# power_test.net
KiCad netlist of a schematic drawn in EAGLE
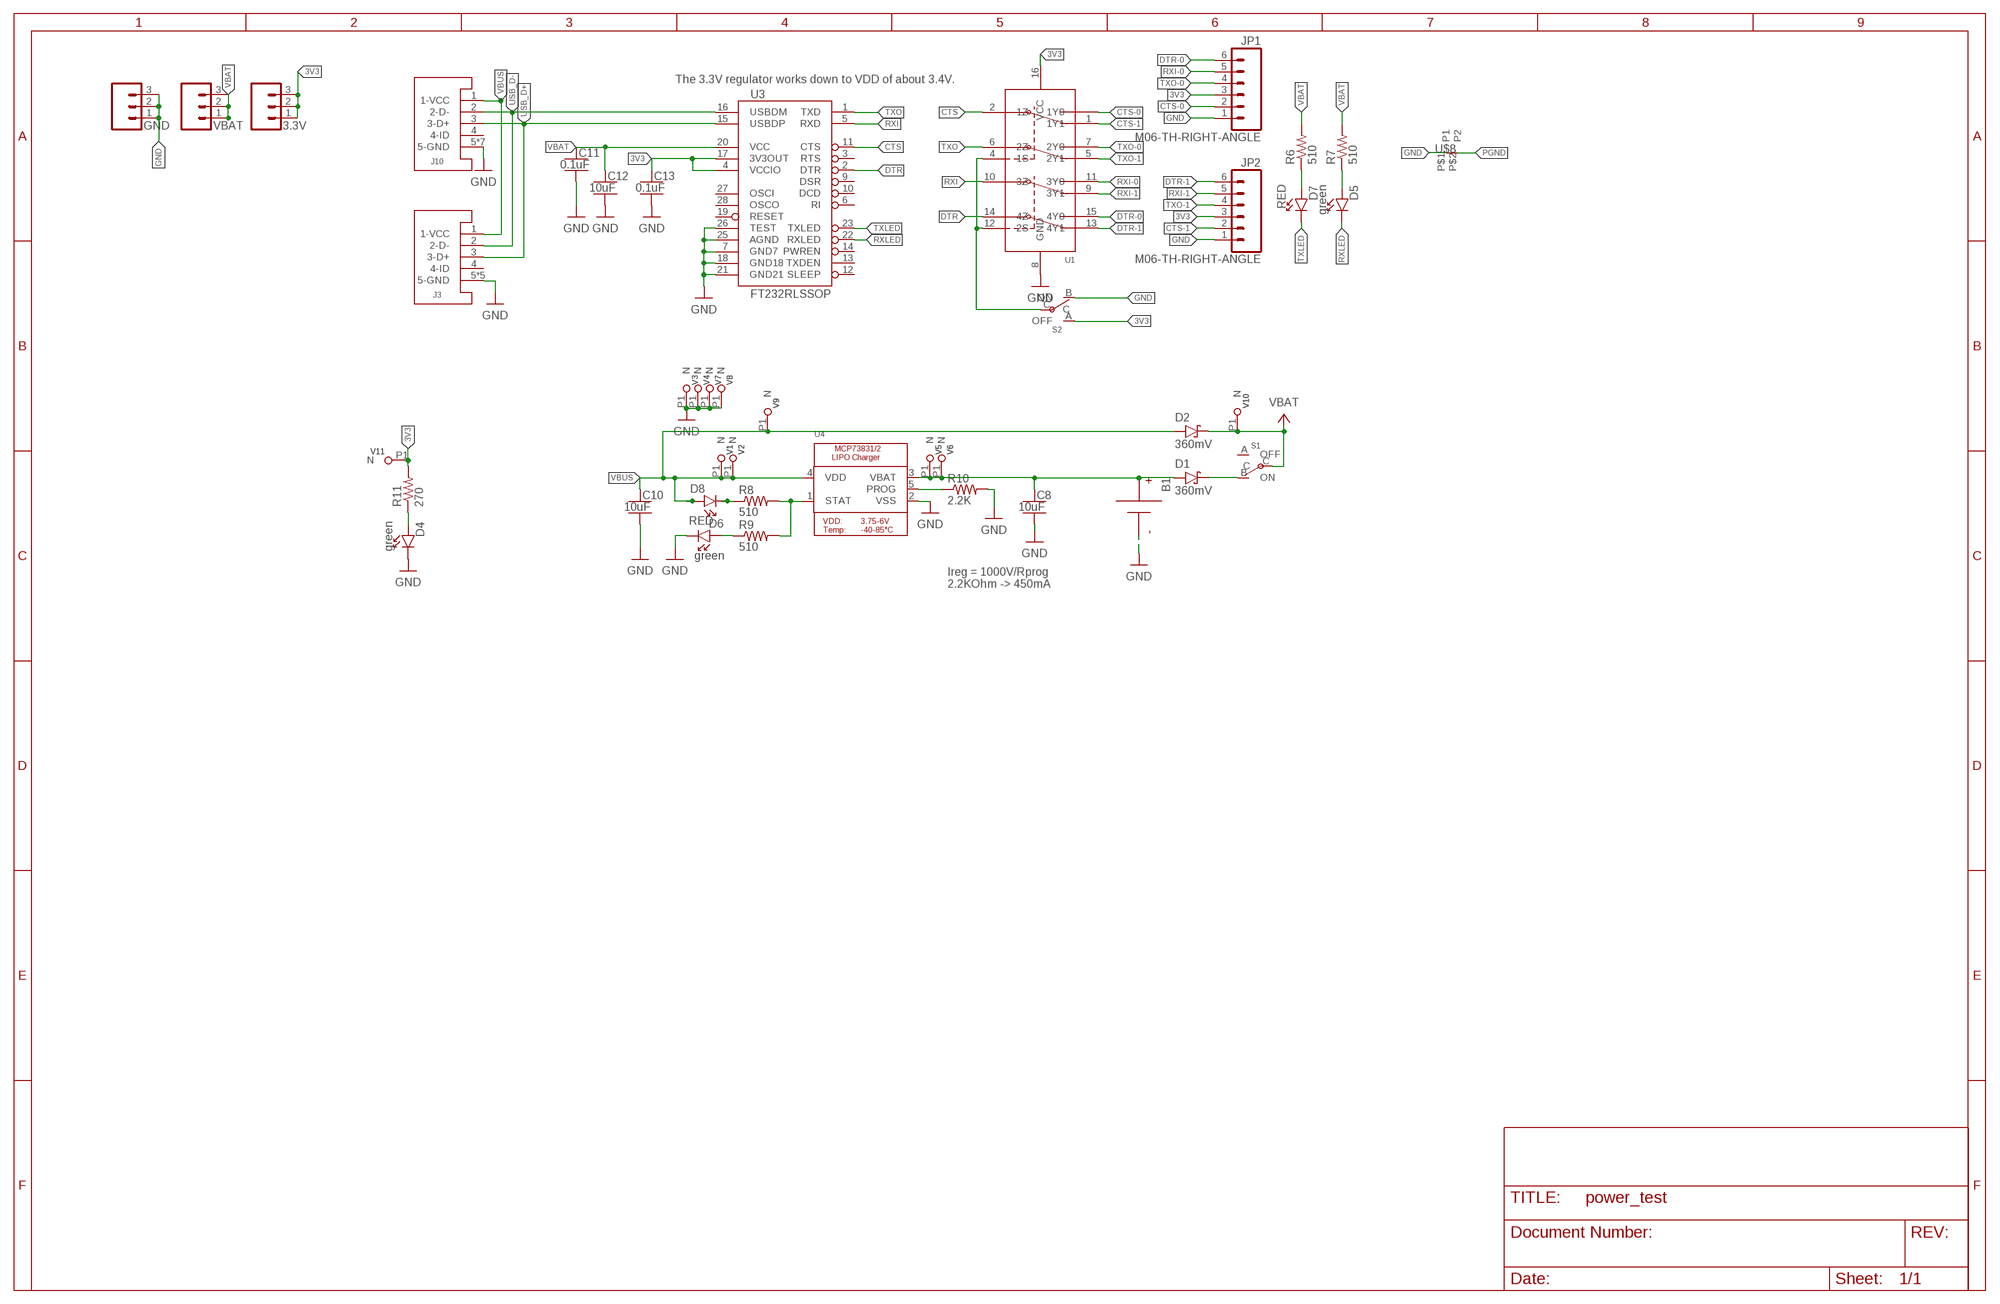
[diagram p0: schematic, sheet 1]

(export (version "E")
  (design (tool "Eeschema 10.0.6"))
  (components
    (comp (ref "3.3V")
      (value "HEADER-0.1IN-3POS-MALE")
      (footprint "eagle-import:HDRV3W63P254_3X1_762X254H838_HS")
      (libsource (lib "eagle-import") (part "HEADER-0.1IN-3POS-MALE"))
    )
    (comp (ref "B1")
      (value "BATTERY")
      (footprint "eagle-import:BATTERY-TERMINALS")
      (fields (field (name "CREATOR") "Swanson"))
      (libsource (lib "eagle-import") (part "BATTERY"))
    )
    (comp (ref "C8")
      (value "10uF")
      (footprint "eagle-import:CAPC2012X140_HS")
      (fields
        (field (name "MFR") "TDK Corporation")
        (field (name "MPN") "C2012X5R1E106K085AC")
        (field (name "CREATOR") "Swanson")
        (field (name "REVIEWER") "Swanson")
      )
      (libsource (lib "eagle-import") (part "CAPACITOR-NP_SMD-2012-0805_CERAMIC-10UF"))
    )
    (comp (ref "C10")
      (value "10uF")
      (footprint "eagle-import:CAPC2012X140_HS")
      (fields
        (field (name "MFR") "TDK Corporation")
        (field (name "MPN") "C2012X5R1E106K085AC")
        (field (name "CREATOR") "Swanson")
        (field (name "REVIEWER") "Swanson")
      )
      (libsource (lib "eagle-import") (part "CAPACITOR-NP_SMD-2012-0805_CERAMIC-10UF"))
    )
    (comp (ref "C11")
      (value "0.1uF")
      (footprint "eagle-import:CAPC2012X140_HS")
      (fields
        (field (name "MFR") "TDK")
        (field (name "MPN") "C2012X7R2A104K125AA")
        (field (name "CREATOR") "Swanson")
        (field (name "REVIEWER") "Swanson")
      )
      (libsource (lib "eagle-import") (part "CAPACITOR-NP_SMD-2012-0805_CERAMIC-0.1UF"))
    )
    (comp (ref "C12")
      (value "10uF")
      (footprint "eagle-import:CAPC2012X140_HS")
      (fields
        (field (name "MFR") "TDK Corporation")
        (field (name "MPN") "C2012X5R1E106K085AC")
        (field (name "CREATOR") "Swanson")
        (field (name "REVIEWER") "Swanson")
      )
      (libsource (lib "eagle-import") (part "CAPACITOR-NP_SMD-2012-0805_CERAMIC-10UF"))
    )
    (comp (ref "C13")
      (value "0.1uF")
      (footprint "eagle-import:CAPC2012X140_HS")
      (fields
        (field (name "MFR") "TDK")
        (field (name "MPN") "C2012X7R2A104K125AA")
        (field (name "CREATOR") "Swanson")
        (field (name "REVIEWER") "Swanson")
      )
      (libsource (lib "eagle-import") (part "CAPACITOR-NP_SMD-2012-0805_CERAMIC-0.1UF"))
    )
    (comp (ref "D1")
      (value "360mV")
      (footprint "eagle-import:SOD3716X135_HS")
      (fields
        (field (name "MFR") "Toshiba Semiconductor and Storage")
        (field (name "MPN") "CRS08(TE85L,Q,M)")
        (field (name "CREATOR") "Swanson")
        (field (name "REVIEWER") "Swanson")
      )
      (libsource (lib "eagle-import") (part "DIODE-SCHOTTKY_SMD-SOD123-360MV"))
    )
    (comp (ref "D2")
      (value "360mV")
      (footprint "eagle-import:SOD3716X135_HS")
      (fields
        (field (name "MFR") "Toshiba Semiconductor and Storage")
        (field (name "MPN") "CRS08(TE85L,Q,M)")
        (field (name "CREATOR") "Swanson")
        (field (name "REVIEWER") "Swanson")
      )
      (libsource (lib "eagle-import") (part "DIODE-SCHOTTKY_SMD-SOD123-360MV"))
    )
    (comp (ref "D4")
      (value "green")
      (footprint "eagle-import:LEDSC125X200X120-2_HS")
      (fields
        (field (name "MFR") "Lite-On Inc")
        (field (name "MPN") "LTST-C170GKT")
        (field (name "CREATOR") "Swanson")
        (field (name "REVIEWER") "Swanson")
      )
      (libsource (lib "eagle-import") (part "DIODE-LED_SMD-2012-0805-GREEN"))
    )
    (comp (ref "D5")
      (value "green")
      (footprint "eagle-import:LEDSC125X200X120-2_HS")
      (fields
        (field (name "MFR") "Lite-On Inc")
        (field (name "MPN") "LTST-C170GKT")
        (field (name "CREATOR") "Swanson")
        (field (name "REVIEWER") "Swanson")
      )
      (libsource (lib "eagle-import") (part "DIODE-LED_SMD-2012-0805-GREEN"))
    )
    (comp (ref "D6")
      (value "green")
      (footprint "eagle-import:LEDSC125X200X120-2_HS")
      (fields
        (field (name "MFR") "Lite-On Inc")
        (field (name "MPN") "LTST-C170GKT")
        (field (name "CREATOR") "Swanson")
        (field (name "REVIEWER") "Swanson")
      )
      (libsource (lib "eagle-import") (part "DIODE-LED_SMD-2012-0805-GREEN"))
    )
    (comp (ref "D7")
      (value "RED")
      (footprint "eagle-import:LEDSC125X200X120-2_HS")
      (fields (field (name "CREATOR") "Swanson"))
      (libsource (lib "eagle-import") (part "DIODE-LED_SMD-2012-0805-RED"))
    )
    (comp (ref "D8")
      (value "RED")
      (footprint "eagle-import:LEDSC125X200X120-2_HS")
      (fields (field (name "CREATOR") "Swanson"))
      (libsource (lib "eagle-import") (part "DIODE-LED_SMD-2012-0805-RED"))
    )
    (comp (ref "GND")
      (value "HEADER-0.1IN-3POS-MALE")
      (footprint "eagle-import:HDRV3W63P254_3X1_762X254H838_HS")
      (libsource (lib "eagle-import") (part "HEADER-0.1IN-3POS-MALE"))
    )
    (comp (ref "J3")
      (value "USB-MICROB-EDAC-690-005-299-043")
      (footprint "eagle-import:USB-MINIB-EDAC-690-005-299-043")
      (fields (field (name "CREATOR") "Swanson"))
      (libsource (lib "eagle-import") (part "USB-MICROB-EDAC-690-005-299-043"))
    )
    (comp (ref "J10")
      (value "USB-MICROA-AMPHENOL-10118192-0001LF")
      (footprint "eagle-import:USB-MICROA-10118192-0001LF")
      (fields (field (name "CREATOR") "Swanson"))
      (libsource (lib "eagle-import") (part "USB-MICROA-AMPHENOL-10118192-0001LF"))
    )
    (comp (ref "JP1")
      (value "M06-TH-RIGHT-ANGLE")
      (footprint "eagle-import:1X06-SIP-RIGHT-ANGLE")
      (libsource (lib "eagle-import") (part "M06-TH-RIGHT-ANGLE"))
    )
    (comp (ref "JP2")
      (value "M06-TH-RIGHT-ANGLE")
      (footprint "eagle-import:1X06-SIP-RIGHT-ANGLE")
      (libsource (lib "eagle-import") (part "M06-TH-RIGHT-ANGLE"))
    )
    (comp (ref "R6")
      (value "510")
      (footprint "eagle-import:RESC2012X60_HS")
      (libsource (lib "eagle-import") (part "RESISTOR_SMD-2012-0805-510"))
    )
    (comp (ref "R7")
      (value "510")
      (footprint "eagle-import:RESC2012X60_HS")
      (libsource (lib "eagle-import") (part "RESISTOR_SMD-2012-0805-510"))
    )
    (comp (ref "R8")
      (value "510")
      (footprint "eagle-import:RESC2012X60_HS")
      (libsource (lib "eagle-import") (part "RESISTOR_SMD-2012-0805-510"))
    )
    (comp (ref "R9")
      (value "510")
      (footprint "eagle-import:RESC2012X60_HS")
      (libsource (lib "eagle-import") (part "RESISTOR_SMD-2012-0805-510"))
    )
    (comp (ref "R10")
      (value "2.2K")
      (footprint "eagle-import:RESC2012X60_HS")
      (libsource (lib "eagle-import") (part "RESISTOR_SMD-2012-0805-2.2K"))
    )
    (comp (ref "R11")
      (value "270")
      (footprint "eagle-import:RESC2012X60_HS")
      (libsource (lib "eagle-import") (part "RESISTOR_SMD-2012-0805-270"))
    )
    (comp (ref "S1")
      (value "POWER-SWITCH-MFS201N-9-ZJS102011SAQN")
      (footprint "eagle-import:JS102011SAQN")
      (fields (field (name "CREATOR") "Swanson"))
      (libsource (lib "eagle-import") (part "POWER-SWITCH-MFS201N-9-ZJS102011SAQN"))
    )
    (comp (ref "S2")
      (value "POWER-SWITCH-MFS201N-9-ZJS102011SAQN")
      (footprint "eagle-import:JS102011SAQN")
      (fields (field (name "CREATOR") "Swanson"))
      (libsource (lib "eagle-import") (part "POWER-SWITCH-MFS201N-9-ZJS102011SAQN"))
    )
    (comp (ref "U$8")
      (value "NET_BRIDGE")
      (footprint "eagle-import:NET_BRIDGE")
      (fields
        (field (name "MFR") "Digikey")
        (field (name "MPN") "0")
        (field (name "CREATOR") "Michael Gonzalez")
      )
      (libsource (lib "eagle-import") (part "NET_BRIDGE"))
    )
    (comp (ref "U1")
      (value "DPDT-X2")
      (footprint "eagle-import:SOP65P640X110-16")
      (fields (field (name "CREATOR") "Swanson"))
      (libsource (lib "eagle-import") (part "DPDT-X2"))
    )
    (comp (ref "U3")
      (value "FT232RLSSOP")
      (footprint "eagle-import:SSOP28DB")
      (fields (field (name "CREATOR") "Swanson"))
      (libsource (lib "eagle-import") (part "FT232RLSSOP"))
    )
    (comp (ref "U4")
      (value "MCP73831T-2ACI/OT")
      (footprint "eagle-import:SOT23-5")
      (fields (field (name "CREATOR") "Adafruit"))
      (libsource (lib "eagle-import") (part "MCP73831/2"))
    )
    (comp (ref "V1")
      (value "LOCKED-VIA-0.2")
      (footprint "eagle-import:VIA-0.2MM")
      (fields (field (name "CREATOR") "Swanson"))
      (libsource (lib "eagle-import") (part "LOCKED-VIA-0.2"))
    )
    (comp (ref "V2")
      (value "LOCKED-VIA-0.2")
      (footprint "eagle-import:VIA-0.2MM")
      (fields (field (name "CREATOR") "Swanson"))
      (libsource (lib "eagle-import") (part "LOCKED-VIA-0.2"))
    )
    (comp (ref "V3")
      (value "LOCKED-VIA-0.2")
      (footprint "eagle-import:VIA-0.2MM")
      (fields (field (name "CREATOR") "Swanson"))
      (libsource (lib "eagle-import") (part "LOCKED-VIA-0.2"))
    )
    (comp (ref "V4")
      (value "LOCKED-VIA-0.2")
      (footprint "eagle-import:VIA-0.2MM")
      (fields (field (name "CREATOR") "Swanson"))
      (libsource (lib "eagle-import") (part "LOCKED-VIA-0.2"))
    )
    (comp (ref "V5")
      (value "LOCKED-VIA-0.2")
      (footprint "eagle-import:VIA-0.2MM")
      (fields (field (name "CREATOR") "Swanson"))
      (libsource (lib "eagle-import") (part "LOCKED-VIA-0.2"))
    )
    (comp (ref "V6")
      (value "LOCKED-VIA-0.2")
      (footprint "eagle-import:VIA-0.2MM")
      (fields (field (name "CREATOR") "Swanson"))
      (libsource (lib "eagle-import") (part "LOCKED-VIA-0.2"))
    )
    (comp (ref "V7")
      (value "LOCKED-VIA-0.2")
      (footprint "eagle-import:VIA-0.2MM")
      (fields (field (name "CREATOR") "Swanson"))
      (libsource (lib "eagle-import") (part "LOCKED-VIA-0.2"))
    )
    (comp (ref "V8")
      (value "LOCKED-VIA-0.2")
      (footprint "eagle-import:VIA-0.2MM")
      (fields (field (name "CREATOR") "Swanson"))
      (libsource (lib "eagle-import") (part "LOCKED-VIA-0.2"))
    )
    (comp (ref "V9")
      (value "LOCKED-VIA-0.2")
      (footprint "eagle-import:VIA-0.2MM")
      (fields (field (name "CREATOR") "Swanson"))
      (libsource (lib "eagle-import") (part "LOCKED-VIA-0.2"))
    )
    (comp (ref "V10")
      (value "LOCKED-VIA-0.2")
      (footprint "eagle-import:VIA-0.2MM")
      (fields (field (name "CREATOR") "Swanson"))
      (libsource (lib "eagle-import") (part "LOCKED-VIA-0.2"))
    )
    (comp (ref "V11")
      (value "LOCKED-VIA-0.2")
      (footprint "eagle-import:VIA-0.2MM")
      (fields (field (name "CREATOR") "Swanson"))
      (libsource (lib "eagle-import") (part "LOCKED-VIA-0.2"))
    )
    (comp (ref "VBAT")
      (value "HEADER-0.1IN-3POS-MALE")
      (footprint "eagle-import:HDRV3W63P254_3X1_762X254H838_HS")
      (libsource (lib "eagle-import") (part "HEADER-0.1IN-3POS-MALE"))
    )
  )
  (nets
    (net (code "1") (name "3V3") (class "Default")
      (node (ref "3.3V") (pin "1") (pinfunction "1_1") (pintype "passive"))
      (node (ref "3.3V") (pin "2") (pinfunction "2_2") (pintype "passive"))
      (node (ref "3.3V") (pin "3") (pinfunction "3_3") (pintype "passive"))
      (node (ref "C13") (pin "1") (pinfunction "1_1") (pintype "passive"))
      (node (ref "JP1") (pin "3") (pinfunction "3_3") (pintype "passive"))
      (node (ref "JP2") (pin "3") (pinfunction "3_3") (pintype "passive"))
      (node (ref "R11") (pin "2") (pinfunction "2_2") (pintype "passive"))
      (node (ref "S2") (pin "A") (pinfunction "OFF_A") (pintype "bidirectional"))
      (node (ref "U1") (pin "16") (pinfunction "VCC_16") (pintype "bidirectional"))
      (node (ref "U3") (pin "17") (pinfunction "3V3OUT_17") (pintype "output"))
      (node (ref "U3") (pin "4") (pinfunction "VCCIO_4") (pintype "power_in"))
      (node (ref "V11") (pin "P1") (pinfunction "N_P1") (pintype "bidirectional"))
    )
    (net (code "2") (name "CTS") (class "Default")
      (node (ref "U1") (pin "2") (pinfunction "1Z_2") (pintype "bidirectional"))
      (node (ref "U3") (pin "11") (pinfunction "CTS_11") (pintype "input"))
    )
    (net (code "3") (name "CTS-0") (class "Default")
      (node (ref "JP1") (pin "2") (pinfunction "2_2") (pintype "passive"))
      (node (ref "U1") (pin "3") (pinfunction "1Y0_3") (pintype "bidirectional"))
    )
    (net (code "4") (name "CTS-1") (class "Default")
      (node (ref "JP2") (pin "2") (pinfunction "2_2") (pintype "passive"))
      (node (ref "U1") (pin "1") (pinfunction "1Y1_1") (pintype "bidirectional"))
    )
    (net (code "5") (name "DTR") (class "Default")
      (node (ref "U1") (pin "14") (pinfunction "4Z_14") (pintype "bidirectional"))
      (node (ref "U3") (pin "2") (pinfunction "DTR_2") (pintype "output"))
    )
    (net (code "6") (name "DTR-0") (class "Default")
      (node (ref "JP1") (pin "6") (pinfunction "6_6") (pintype "passive"))
      (node (ref "U1") (pin "15") (pinfunction "4Y0_15") (pintype "bidirectional"))
    )
    (net (code "7") (name "DTR-1") (class "Default")
      (node (ref "JP2") (pin "6") (pinfunction "6_6") (pintype "passive"))
      (node (ref "U1") (pin "13") (pinfunction "4Y1_13") (pintype "bidirectional"))
    )
    (net (code "8") (name "GND") (class "Default")
      (node (ref "B1") (pin "-") (pinfunction "N_-") (pintype "bidirectional"))
      (node (ref "C10") (pin "2") (pinfunction "2_2") (pintype "passive"))
      (node (ref "C11") (pin "2") (pinfunction "2_2") (pintype "passive"))
      (node (ref "C12") (pin "2") (pinfunction "2_2") (pintype "passive"))
      (node (ref "C13") (pin "2") (pinfunction "2_2") (pintype "passive"))
      (node (ref "C8") (pin "2") (pinfunction "2_2") (pintype "passive"))
      (node (ref "D4") (pin "C") (pinfunction "C_C") (pintype "passive"))
      (node (ref "D6") (pin "C") (pinfunction "C_C") (pintype "passive"))
      (node (ref "GND") (pin "1") (pinfunction "1_1") (pintype "passive"))
      (node (ref "GND") (pin "2") (pinfunction "2_2") (pintype "passive"))
      (node (ref "GND") (pin "3") (pinfunction "3_3") (pintype "passive"))
      (node (ref "J10") (pin "10") (pinfunction "5-GND_10") (pintype "bidirectional"))
      (node (ref "J10") (pin "11") (pinfunction "5-GND_11") (pintype "bidirectional"))
      (node (ref "J10") (pin "5") (pinfunction "5-GND_5") (pintype "bidirectional"))
      (node (ref "J10") (pin "6") (pinfunction "5-GND_6") (pintype "bidirectional"))
      (node (ref "J10") (pin "7") (pinfunction "5-GND_7") (pintype "bidirectional"))
      (node (ref "J10") (pin "8") (pinfunction "5-GND_8") (pintype "bidirectional"))
      (node (ref "J10") (pin "9") (pinfunction "5-GND_9") (pintype "bidirectional"))
      (node (ref "J3") (pin "5") (pinfunction "5-GND_5") (pintype "bidirectional"))
      (node (ref "J3") (pin "P6") (pinfunction "5-GND_P6") (pintype "bidirectional"))
      (node (ref "J3") (pin "P7") (pinfunction "5-GND_P7") (pintype "bidirectional"))
      (node (ref "J3") (pin "P8") (pinfunction "5-GND_P8") (pintype "bidirectional"))
      (node (ref "J3") (pin "P9") (pinfunction "5-GND_P9") (pintype "bidirectional"))
      (node (ref "JP1") (pin "1") (pinfunction "1_1") (pintype "passive"))
      (node (ref "JP2") (pin "1") (pinfunction "1_1") (pintype "passive"))
      (node (ref "R10") (pin "2") (pinfunction "2_2") (pintype "passive"))
      (node (ref "S2") (pin "B") (pinfunction "ON_B") (pintype "bidirectional"))
      (node (ref "U$8") (pin "P$1") (pinfunction "P1_P$1") (pintype "bidirectional"))
      (node (ref "U1") (pin "8") (pinfunction "GND_8") (pintype "bidirectional"))
      (node (ref "U3") (pin "18") (pinfunction "GND18_18") (pintype "power_in"))
      (node (ref "U3") (pin "21") (pinfunction "GND21_21") (pintype "power_in"))
      (node (ref "U3") (pin "25") (pinfunction "AGND_25") (pintype "power_in"))
      (node (ref "U3") (pin "26") (pinfunction "TEST_26") (pintype "input"))
      (node (ref "U3") (pin "7") (pinfunction "GND7_7") (pintype "power_in"))
      (node (ref "U4") (pin "2") (pinfunction "VSS_2") (pintype "power_in"))
      (node (ref "V3") (pin "P1") (pinfunction "N_P1") (pintype "bidirectional"))
      (node (ref "V4") (pin "P1") (pinfunction "N_P1") (pintype "bidirectional"))
      (node (ref "V7") (pin "P1") (pinfunction "N_P1") (pintype "bidirectional"))
      (node (ref "V8") (pin "P1") (pinfunction "N_P1") (pintype "bidirectional"))
    )
    (net (code "9") (name "Net-(B1-P)") (class "Default")
      (node (ref "B1") (pin "+") (pinfunction "P_+") (pintype "bidirectional"))
      (node (ref "C8") (pin "1") (pinfunction "1_1") (pintype "passive"))
      (node (ref "D1") (pin "A") (pinfunction "A_A") (pintype "passive"))
      (node (ref "U4") (pin "3") (pinfunction "VBAT_3") (pintype "power_in"))
      (node (ref "V5") (pin "P1") (pinfunction "N_P1") (pintype "bidirectional"))
      (node (ref "V6") (pin "P1") (pinfunction "N_P1") (pintype "bidirectional"))
    )
    (net (code "10") (name "Net-(D4-PadA)") (class "Default")
      (node (ref "D4") (pin "A") (pinfunction "A_A") (pintype "passive"))
      (node (ref "R11") (pin "1") (pinfunction "1_1") (pintype "passive"))
    )
    (net (code "11") (name "Net-(D5-PadA)") (class "Default")
      (node (ref "D5") (pin "A") (pinfunction "A_A") (pintype "passive"))
      (node (ref "R7") (pin "1") (pinfunction "1_1") (pintype "passive"))
    )
    (net (code "12") (name "Net-(D6-PadA)") (class "Default")
      (node (ref "D6") (pin "A") (pinfunction "A_A") (pintype "passive"))
      (node (ref "R9") (pin "1") (pinfunction "1_1") (pintype "passive"))
    )
    (net (code "13") (name "Net-(D7-PadA)") (class "Default")
      (node (ref "D7") (pin "A") (pinfunction "A_A") (pintype "passive"))
      (node (ref "R6") (pin "1") (pinfunction "1_1") (pintype "passive"))
    )
    (net (code "14") (name "Net-(D8-PadC)") (class "Default")
      (node (ref "D8") (pin "C") (pinfunction "C_C") (pintype "passive"))
      (node (ref "R8") (pin "1") (pinfunction "1_1") (pintype "passive"))
    )
    (net (code "15") (name "Net-(S1-ON)") (class "Default")
      (node (ref "D1") (pin "C") (pinfunction "C_C") (pintype "passive"))
      (node (ref "S1") (pin "B") (pinfunction "ON_B") (pintype "bidirectional"))
    )
    (net (code "16") (name "Net-(U1-1S)") (class "Default")
      (node (ref "S2") (pin "C") (pinfunction "C_C") (pintype "bidirectional"))
      (node (ref "U1") (pin "12") (pinfunction "2S_12") (pintype "bidirectional"))
      (node (ref "U1") (pin "4") (pinfunction "1S_4") (pintype "bidirectional"))
    )
    (net (code "17") (name "Net-(U4-PROG)") (class "Default")
      (node (ref "R10") (pin "1") (pinfunction "1_1") (pintype "passive"))
      (node (ref "U4") (pin "5") (pinfunction "PROG_5") (pintype "input"))
    )
    (net (code "18") (name "Net-(U4-STAT)") (class "Default")
      (node (ref "R8") (pin "2") (pinfunction "2_2") (pintype "passive"))
      (node (ref "R9") (pin "2") (pinfunction "2_2") (pintype "passive"))
      (node (ref "U4") (pin "1") (pinfunction "STAT_1") (pintype "output"))
    )
    (net (code "19") (name "PGND") (class "Default")
      (node (ref "U$8") (pin "P$2") (pinfunction "P2_P$2") (pintype "bidirectional"))
    )
    (net (code "20") (name "RXI") (class "Default")
      (node (ref "U1") (pin "10") (pinfunction "3Z_10") (pintype "bidirectional"))
      (node (ref "U3") (pin "5") (pinfunction "RXD_5") (pintype "input"))
    )
    (net (code "21") (name "RXI-0") (class "Default")
      (node (ref "JP1") (pin "5") (pinfunction "5_5") (pintype "passive"))
      (node (ref "U1") (pin "11") (pinfunction "3Y0_11") (pintype "bidirectional"))
    )
    (net (code "22") (name "RXI-1") (class "Default")
      (node (ref "JP2") (pin "5") (pinfunction "5_5") (pintype "passive"))
      (node (ref "U1") (pin "9") (pinfunction "3Y1_9") (pintype "bidirectional"))
    )
    (net (code "23") (name "RXLED") (class "Default")
      (node (ref "D5") (pin "C") (pinfunction "C_C") (pintype "passive"))
      (node (ref "U3") (pin "22") (pinfunction "RXLED_22") (pintype "input"))
    )
    (net (code "24") (name "TXLED") (class "Default")
      (node (ref "D7") (pin "C") (pinfunction "C_C") (pintype "passive"))
      (node (ref "U3") (pin "23") (pinfunction "TXLED_23") (pintype "input"))
    )
    (net (code "25") (name "TXO") (class "Default")
      (node (ref "U1") (pin "6") (pinfunction "2Z_6") (pintype "bidirectional"))
      (node (ref "U3") (pin "1") (pinfunction "TXD_1") (pintype "output"))
    )
    (net (code "26") (name "TXO-0") (class "Default")
      (node (ref "JP1") (pin "4") (pinfunction "4_4") (pintype "passive"))
      (node (ref "U1") (pin "7") (pinfunction "2Y0_7") (pintype "bidirectional"))
    )
    (net (code "27") (name "TXO-1") (class "Default")
      (node (ref "JP2") (pin "4") (pinfunction "4_4") (pintype "passive"))
      (node (ref "U1") (pin "5") (pinfunction "2Y1_5") (pintype "bidirectional"))
    )
    (net (code "28") (name "USB_D+") (class "Default")
      (node (ref "J10") (pin "3") (pinfunction "3-D+_3") (pintype "bidirectional"))
      (node (ref "J3") (pin "3") (pinfunction "3-D+_3") (pintype "bidirectional"))
      (node (ref "U3") (pin "15") (pinfunction "USBDP_15") (pintype "bidirectional"))
    )
    (net (code "29") (name "USB_D-") (class "Default")
      (node (ref "J10") (pin "2") (pinfunction "2-D-_2") (pintype "bidirectional"))
      (node (ref "J3") (pin "2") (pinfunction "2-D-_2") (pintype "bidirectional"))
      (node (ref "U3") (pin "16") (pinfunction "USBDM_16") (pintype "bidirectional"))
    )
    (net (code "30") (name "VBAT") (class "Default")
      (node (ref "C11") (pin "1") (pinfunction "1_1") (pintype "passive"))
      (node (ref "C12") (pin "1") (pinfunction "1_1") (pintype "passive"))
      (node (ref "D2") (pin "C") (pinfunction "C_C") (pintype "passive"))
      (node (ref "R6") (pin "2") (pinfunction "2_2") (pintype "passive"))
      (node (ref "R7") (pin "2") (pinfunction "2_2") (pintype "passive"))
      (node (ref "S1") (pin "C") (pinfunction "C_C") (pintype "bidirectional"))
      (node (ref "U3") (pin "20") (pinfunction "VCC_20") (pintype "power_in"))
      (node (ref "V10") (pin "P1") (pinfunction "N_P1") (pintype "bidirectional"))
      (node (ref "VBAT") (pin "1") (pinfunction "1_1") (pintype "passive"))
      (node (ref "VBAT") (pin "2") (pinfunction "2_2") (pintype "passive"))
      (node (ref "VBAT") (pin "3") (pinfunction "3_3") (pintype "passive"))
    )
    (net (code "31") (name "VBUS") (class "Default")
      (node (ref "C10") (pin "1") (pinfunction "1_1") (pintype "passive"))
      (node (ref "D2") (pin "A") (pinfunction "A_A") (pintype "passive"))
      (node (ref "D8") (pin "A") (pinfunction "A_A") (pintype "passive"))
      (node (ref "J10") (pin "1") (pinfunction "1-VCC_1") (pintype "bidirectional"))
      (node (ref "J3") (pin "1") (pinfunction "1-VCC_1") (pintype "bidirectional"))
      (node (ref "U4") (pin "4") (pinfunction "VDD_4") (pintype "power_in"))
      (node (ref "V1") (pin "P1") (pinfunction "N_P1") (pintype "bidirectional"))
      (node (ref "V2") (pin "P1") (pinfunction "N_P1") (pintype "bidirectional"))
      (node (ref "V9") (pin "P1") (pinfunction "N_P1") (pintype "bidirectional"))
    )
    (net (code "32") (name "unconnected-(J3-4-ID-Pad4)") (class "Default")
      (node (ref "J3") (pin "4") (pinfunction "4-ID_4") (pintype "bidirectional"))
    )
    (net (code "33") (name "unconnected-(J10-4-ID-Pad4)") (class "Default")
      (node (ref "J10") (pin "4") (pinfunction "4-ID_4") (pintype "bidirectional"))
    )
    (net (code "34") (name "unconnected-(S1-OFF-PadA)") (class "Default")
      (node (ref "S1") (pin "A") (pinfunction "OFF_A") (pintype "bidirectional"))
    )
    (net (code "35") (name "unconnected-(U3-DCD-Pad10)") (class "Default")
      (node (ref "U3") (pin "10") (pinfunction "DCD_10") (pintype "input"))
    )
    (net (code "36") (name "unconnected-(U3-DSR-Pad9)") (class "Default")
      (node (ref "U3") (pin "9") (pinfunction "DSR_9") (pintype "input"))
    )
    (net (code "37") (name "unconnected-(U3-OSCI-Pad27)") (class "Default")
      (node (ref "U3") (pin "27") (pinfunction "OSCI_27") (pintype "input"))
    )
    (net (code "38") (name "unconnected-(U3-OSCO-Pad28)") (class "Default")
      (node (ref "U3") (pin "28") (pinfunction "OSCO_28") (pintype "output"))
    )
    (net (code "39") (name "unconnected-(U3-PWREN-Pad14)") (class "Default")
      (node (ref "U3") (pin "14") (pinfunction "PWREN_14") (pintype "input"))
    )
    (net (code "40") (name "unconnected-(U3-RESET-Pad19)") (class "Default")
      (node (ref "U3") (pin "19") (pinfunction "RESET_19") (pintype "input"))
    )
    (net (code "41") (name "unconnected-(U3-RI-Pad6)") (class "Default")
      (node (ref "U3") (pin "6") (pinfunction "RI_6") (pintype "input"))
    )
    (net (code "42") (name "unconnected-(U3-RTS-Pad3)") (class "Default")
      (node (ref "U3") (pin "3") (pinfunction "RTS_3") (pintype "output"))
    )
    (net (code "43") (name "unconnected-(U3-SLEEP-Pad12)") (class "Default")
      (node (ref "U3") (pin "12") (pinfunction "SLEEP_12") (pintype "input"))
    )
    (net (code "44") (name "unconnected-(U3-TXDEN-Pad13)") (class "Default")
      (node (ref "U3") (pin "13") (pinfunction "TXDEN_13") (pintype "input"))
    )
  )
)
